# 4-Fach-Anzeige.net
KiCad netlist of a schematic drawn in EAGLE
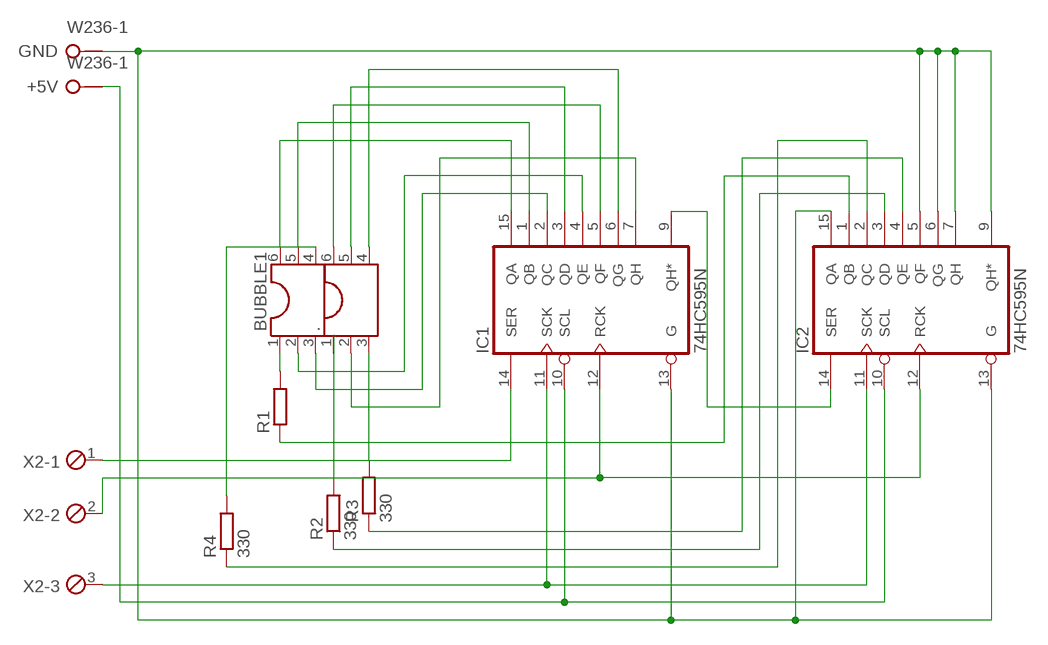
[diagram p0: schematic, sheet 1]

(export (version "E")
  (design (tool "Eeschema 10.0.6"))
  (components
    (comp (ref "+5V")
      (value "W236-1")
      (footprint "eagle-import:W236-1")
      (libsource (lib "eagle-import") (part "W236-1"))
    )
    (comp (ref ".")
      (value "DIL6")
      (footprint "eagle-import:DIL06")
      (libsource (lib "eagle-import") (part "DIL6"))
    )
    (comp (ref "BUBBLE1")
      (value "DIL6")
      (footprint "eagle-import:DIL06")
      (libsource (lib "eagle-import") (part "DIL6"))
    )
    (comp (ref "GND")
      (value "W236-1")
      (footprint "eagle-import:W236-1")
      (libsource (lib "eagle-import") (part "W236-1"))
    )
    (comp (ref "IC1")
      (value "74HC595N")
      (footprint "eagle-import:DIL16")
      (libsource (lib "eagle-import") (part "74595NHC"))
    )
    (comp (ref "IC2")
      (value "74HC595N")
      (footprint "eagle-import:DIL16")
      (libsource (lib "eagle-import") (part "74595NHC"))
    )
    (comp (ref "R1")
      (value "R-EU_0207/10")
      (footprint "eagle-import:0207_10")
      (libsource (lib "eagle-import") (part "R-EU_0207/10"))
    )
    (comp (ref "R2")
      (value "330")
      (footprint "eagle-import:0207_10")
      (libsource (lib "eagle-import") (part "R-EU_0207/10"))
    )
    (comp (ref "R3")
      (value "330")
      (footprint "eagle-import:0207_10")
      (libsource (lib "eagle-import") (part "R-EU_0207/10"))
    )
    (comp (ref "R4")
      (value "330")
      (footprint "eagle-import:0207_10")
      (libsource (lib "eagle-import") (part "R-EU_0207/10"))
    )
    (comp (ref "X2")
      (value "MPT3")
      (footprint "eagle-import:3POL254")
      (libsource (lib "eagle-import") (part "MPT3"))
    )
  )
  (nets
    (net (code "1") (name "Net-(+5V-KL1)") (class "Default")
      (node (ref "+5V") (pin "1") (pinfunction "KL1_1") (pintype "passive"))
      (node (ref "IC1") (pin "10") (pinfunction "SCL_10") (pintype "input"))
      (node (ref "IC2") (pin "10") (pinfunction "SCL_10") (pintype "input"))
    )
    (net (code "2") (name "Net-(.-Pad3)") (class "Default")
      (node (ref ".") (pin "3") (pinfunction "3_3") (pintype "passive"))
      (node (ref "R3") (pin "2") (pinfunction "2_2") (pintype "passive"))
    )
    (net (code "3") (name "Net-(BUBBLE1-Pad1)") (class "Default")
      (node (ref "BUBBLE1") (pin "1") (pinfunction "1_1") (pintype "passive"))
      (node (ref "R1") (pin "2") (pinfunction "2_2") (pintype "passive"))
    )
    (net (code "4") (name "Net-(BUBBLE1-Pad4)") (class "Default")
      (node (ref "BUBBLE1") (pin "4") (pinfunction "4_4") (pintype "passive"))
      (node (ref "R4") (pin "2") (pinfunction "2_2") (pintype "passive"))
    )
    (net (code "5") (name "Net-(GND-KL1)") (class "Default")
      (node (ref "GND") (pin "1") (pinfunction "KL1_1") (pintype "passive"))
      (node (ref "IC1") (pin "13") (pinfunction "G_13") (pintype "input"))
      (node (ref "IC2") (pin "13") (pinfunction "G_13") (pintype "input"))
      (node (ref "IC2") (pin "15") (pinfunction "QA_15") (pintype "tri_state"))
      (node (ref "IC2") (pin "5") (pinfunction "QF_5") (pintype "tri_state"))
      (node (ref "IC2") (pin "6") (pinfunction "QG_6") (pintype "tri_state"))
      (node (ref "IC2") (pin "7") (pinfunction "QH_7") (pintype "tri_state"))
      (node (ref "IC2") (pin "9") (pinfunction "QH*_9") (pintype "tri_state"))
    )
    (net (code "6") (name "Net-(IC1A-QA)") (class "Default")
      (node (ref "BUBBLE1") (pin "6") (pinfunction "6_6") (pintype "passive"))
      (node (ref "IC1") (pin "15") (pinfunction "QA_15") (pintype "tri_state"))
    )
    (net (code "7") (name "Net-(IC1A-QB)") (class "Default")
      (node (ref "BUBBLE1") (pin "5") (pinfunction "5_5") (pintype "passive"))
      (node (ref "IC1") (pin "1") (pinfunction "QB_1") (pintype "tri_state"))
    )
    (net (code "8") (name "Net-(IC1A-QC)") (class "Default")
      (node (ref "BUBBLE1") (pin "3") (pinfunction "3_3") (pintype "passive"))
      (node (ref "IC1") (pin "2") (pinfunction "QC_2") (pintype "tri_state"))
    )
    (net (code "9") (name "Net-(IC1A-QD)") (class "Default")
      (node (ref ".") (pin "5") (pinfunction "5_5") (pintype "passive"))
      (node (ref "IC1") (pin "3") (pinfunction "QD_3") (pintype "tri_state"))
    )
    (net (code "10") (name "Net-(IC1A-QE)") (class "Default")
      (node (ref "BUBBLE1") (pin "2") (pinfunction "2_2") (pintype "passive"))
      (node (ref "IC1") (pin "4") (pinfunction "QE_4") (pintype "tri_state"))
    )
    (net (code "11") (name "Net-(IC1A-QF)") (class "Default")
      (node (ref ".") (pin "6") (pinfunction "6_6") (pintype "passive"))
      (node (ref "IC1") (pin "5") (pinfunction "QF_5") (pintype "tri_state"))
    )
    (net (code "12") (name "Net-(IC1A-QG)") (class "Default")
      (node (ref ".") (pin "4") (pinfunction "4_4") (pintype "passive"))
      (node (ref "IC1") (pin "6") (pinfunction "QG_6") (pintype "tri_state"))
    )
    (net (code "13") (name "Net-(IC1A-QH)") (class "Default")
      (node (ref ".") (pin "2") (pinfunction "2_2") (pintype "passive"))
      (node (ref "IC1") (pin "7") (pinfunction "QH_7") (pintype "tri_state"))
    )
    (net (code "14") (name "Net-(IC1A-QH*)") (class "Default")
      (node (ref "IC1") (pin "9") (pinfunction "QH*_9") (pintype "tri_state"))
      (node (ref "IC2") (pin "14") (pinfunction "SER_14") (pintype "input"))
    )
    (net (code "15") (name "Net-(IC1A-RCK)") (class "Default")
      (node (ref "IC1") (pin "12") (pinfunction "RCK_12") (pintype "input"))
      (node (ref "IC2") (pin "12") (pinfunction "RCK_12") (pintype "input"))
      (node (ref "X2") (pin "2") (pinfunction "1_2") (pintype "passive"))
    )
    (net (code "16") (name "Net-(IC1A-SCK)") (class "Default")
      (node (ref "IC1") (pin "11") (pinfunction "SCK_11") (pintype "input"))
      (node (ref "IC2") (pin "11") (pinfunction "SCK_11") (pintype "input"))
      (node (ref "X2") (pin "3") (pinfunction "1_3") (pintype "passive"))
    )
    (net (code "17") (name "Net-(IC1A-SER)") (class "Default")
      (node (ref "IC1") (pin "14") (pinfunction "SER_14") (pintype "input"))
      (node (ref "X2") (pin "1") (pinfunction "1_1") (pintype "passive"))
    )
    (net (code "18") (name "Net-(IC2A-QB)") (class "Default")
      (node (ref "IC2") (pin "1") (pinfunction "QB_1") (pintype "tri_state"))
      (node (ref "R1") (pin "1") (pinfunction "1_1") (pintype "passive"))
    )
    (net (code "19") (name "Net-(IC2A-QC)") (class "Default")
      (node (ref "IC2") (pin "2") (pinfunction "QC_2") (pintype "tri_state"))
      (node (ref "R4") (pin "1") (pinfunction "1_1") (pintype "passive"))
    )
    (net (code "20") (name "Net-(IC2A-QD)") (class "Default")
      (node (ref "IC2") (pin "3") (pinfunction "QD_3") (pintype "tri_state"))
      (node (ref "R2") (pin "1") (pinfunction "1_1") (pintype "passive"))
    )
    (net (code "21") (name "Net-(IC2A-QE)") (class "Default")
      (node (ref "IC2") (pin "4") (pinfunction "QE_4") (pintype "tri_state"))
      (node (ref "R3") (pin "1") (pinfunction "1_1") (pintype "passive"))
    )
    (net (code "22") (name "unconnected-(+5V-KL2-Pad2)") (class "Default")
      (node (ref "+5V") (pin "2") (pinfunction "KL2_2") (pintype "passive"))
    )
    (net (code "23") (name "unconnected-(.-Pad1)") (class "Default")
      (node (ref ".") (pin "1") (pinfunction "1_1") (pintype "passive"))
    )
    (net (code "24") (name "unconnected-(GND-KL2-Pad2)") (class "Default")
      (node (ref "GND") (pin "2") (pinfunction "KL2_2") (pintype "passive"))
    )
    (net (code "25") (name "unconnected-(R2-Pad2)") (class "Default")
      (node (ref "R2") (pin "2") (pinfunction "2_2") (pintype "passive"))
    )
  )
)
